# main.net
KiCad netlist of a schematic drawn in EAGLE
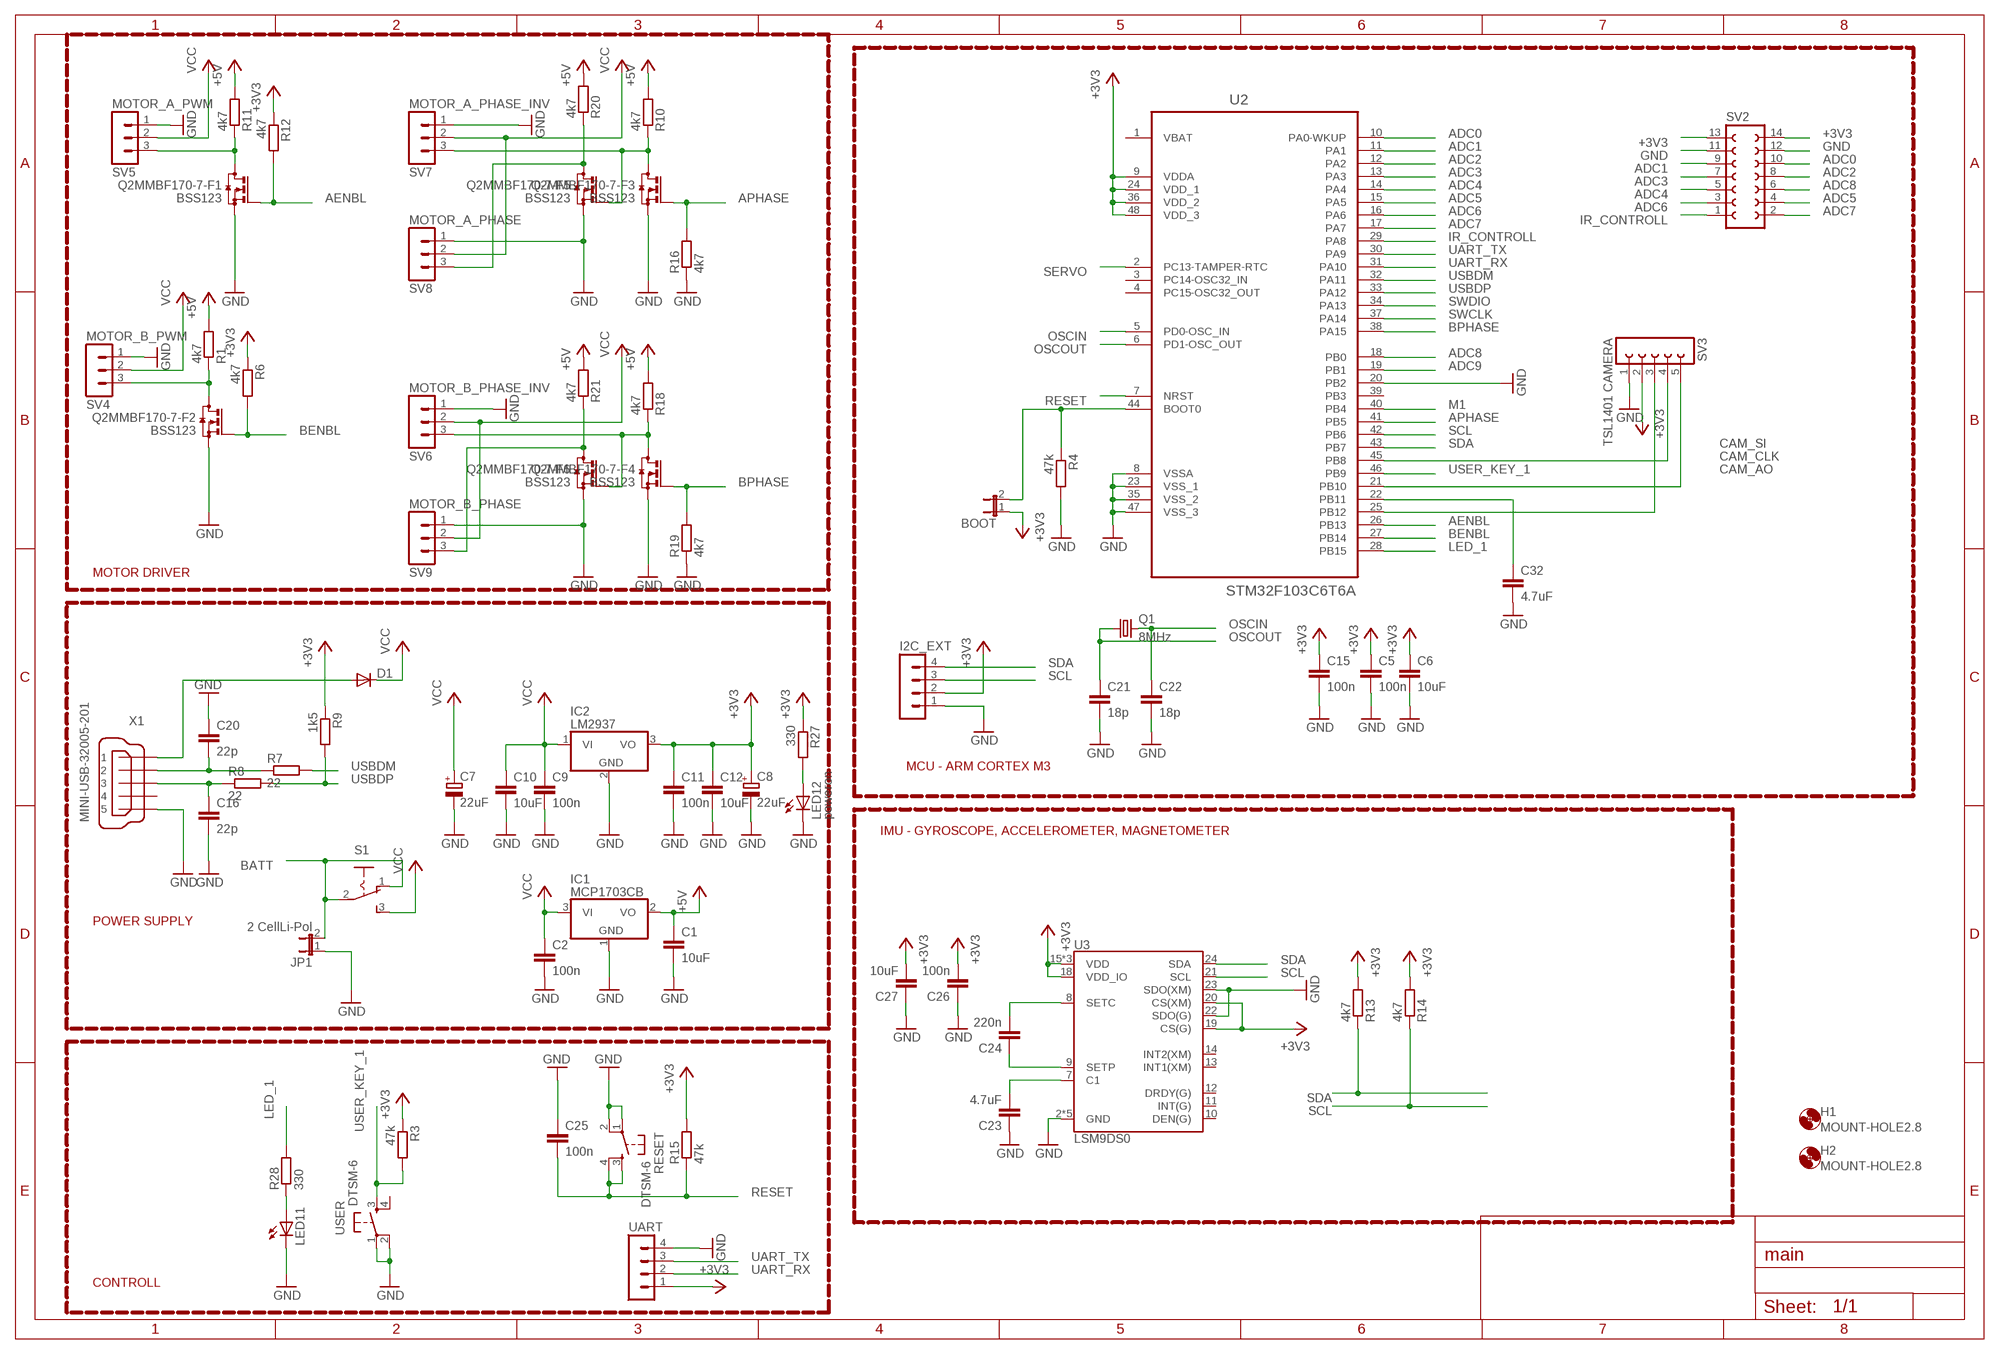
[diagram p0: schematic, sheet 1]

(export (version "E")
  (design (tool "Eeschema 10.0.6"))
  (components
    (comp (ref "BOOT")
      (value "JP1E")
      (footprint "eagle-import:JP1")
      (libsource (lib "eagle-import") (part "JP1E"))
    )
    (comp (ref "C1")
      (value "10uF")
      (footprint "eagle-import:C0805")
      (libsource (lib "eagle-import") (part "C-EUC0805"))
    )
    (comp (ref "C2")
      (value "100n")
      (footprint "eagle-import:C0805")
      (libsource (lib "eagle-import") (part "C-EUC0805"))
    )
    (comp (ref "C5")
      (value "100n")
      (footprint "eagle-import:C0805")
      (libsource (lib "eagle-import") (part "C-EUC0805"))
    )
    (comp (ref "C6")
      (value "10uF")
      (footprint "eagle-import:C0805")
      (libsource (lib "eagle-import") (part "C-EUC0805"))
    )
    (comp (ref "C7")
      (value "22uF")
      (footprint "eagle-import:153CLV-0505")
      (libsource (lib "eagle-import") (part "CPOL-EU153CLV-0505"))
    )
    (comp (ref "C8")
      (value "22uF")
      (footprint "eagle-import:153CLV-0505")
      (libsource (lib "eagle-import") (part "CPOL-EU153CLV-0505"))
    )
    (comp (ref "C9")
      (value "100n")
      (footprint "eagle-import:C0805")
      (libsource (lib "eagle-import") (part "C-EUC0805"))
    )
    (comp (ref "C10")
      (value "10uF")
      (footprint "eagle-import:C0805")
      (libsource (lib "eagle-import") (part "C-EUC0805"))
    )
    (comp (ref "C11")
      (value "100n")
      (footprint "eagle-import:C0805")
      (libsource (lib "eagle-import") (part "C-EUC0805"))
    )
    (comp (ref "C12")
      (value "10uF")
      (footprint "eagle-import:C0805")
      (libsource (lib "eagle-import") (part "C-EUC0805"))
    )
    (comp (ref "C15")
      (value "100n")
      (footprint "eagle-import:C0805")
      (libsource (lib "eagle-import") (part "C-EUC0805"))
    )
    (comp (ref "C16")
      (value "22p")
      (footprint "eagle-import:C0805")
      (libsource (lib "eagle-import") (part "C-EUC0805"))
    )
    (comp (ref "C20")
      (value "22p")
      (footprint "eagle-import:C0805")
      (libsource (lib "eagle-import") (part "C-EUC0805"))
    )
    (comp (ref "C21")
      (value "18p")
      (footprint "eagle-import:C0805")
      (libsource (lib "eagle-import") (part "C-EUC0805"))
    )
    (comp (ref "C22")
      (value "18p")
      (footprint "eagle-import:C0805")
      (libsource (lib "eagle-import") (part "C-EUC0805"))
    )
    (comp (ref "C23")
      (value "4.7uF")
      (footprint "eagle-import:C0805")
      (libsource (lib "eagle-import") (part "C-EUC0805"))
    )
    (comp (ref "C24")
      (value "220n")
      (footprint "eagle-import:C0805")
      (libsource (lib "eagle-import") (part "C-EUC0805"))
    )
    (comp (ref "C25")
      (value "100n")
      (footprint "eagle-import:C0805")
      (libsource (lib "eagle-import") (part "C-EUC0805"))
    )
    (comp (ref "C26")
      (value "100n")
      (footprint "eagle-import:C0805")
      (libsource (lib "eagle-import") (part "C-EUC0805"))
    )
    (comp (ref "C27")
      (value "10uF")
      (footprint "eagle-import:C0805")
      (libsource (lib "eagle-import") (part "C-EUC0805"))
    )
    (comp (ref "C32")
      (value "4.7uF")
      (footprint "eagle-import:C0805")
      (libsource (lib "eagle-import") (part "C-EUC0805"))
    )
    (comp (ref "D1")
      (value "DIODE-SMB")
      (footprint "eagle-import:SMB")
      (libsource (lib "eagle-import") (part "DIODE-SMB"))
    )
    (comp (ref "H1")
      (value "MOUNT-HOLE2.8")
      (footprint "eagle-import:2,8")
      (libsource (lib "eagle-import") (part "MOUNT-HOLE2.8"))
    )
    (comp (ref "H2")
      (value "MOUNT-HOLE2.8")
      (footprint "eagle-import:2,8")
      (libsource (lib "eagle-import") (part "MOUNT-HOLE2.8"))
    )
    (comp (ref "I2C_EXT")
      (value "MA04-1")
      (footprint "eagle-import:MA04-1")
      (libsource (lib "eagle-import") (part "MA04-1"))
    )
    (comp (ref "IC1")
      (value "MCP1703CB")
      (footprint "eagle-import:SOT23")
      (libsource (lib "eagle-import") (part "MCP1703CB"))
    )
    (comp (ref "IC2")
      (value "LM2937")
      (footprint "eagle-import:TO263-3")
      (libsource (lib "eagle-import") (part "LM2937"))
    )
    (comp (ref "JP1")
      (value "2 CellLi-Pol")
      (footprint "eagle-import:JP1")
      (libsource (lib "eagle-import") (part "JP1E"))
    )
    (comp (ref "LED11")
      (value "LEDCHIPLED_1206")
      (footprint "eagle-import:CHIPLED_1206")
      (libsource (lib "eagle-import") (part "LEDCHIPLED_1206"))
    )
    (comp (ref "LED12")
      (value "poweron")
      (footprint "eagle-import:CHIPLED_1206")
      (libsource (lib "eagle-import") (part "LEDCHIPLED_1206"))
    )
    (comp (ref "Q1")
      (value "8MHz")
      (footprint "eagle-import:CTS406")
      (libsource (lib "eagle-import") (part "CRYSTALCTS406"))
    )
    (comp (ref "Q2MMBF170-7-F1")
      (value "BSS123")
      (footprint "eagle-import:SOT23")
      (libsource (lib "eagle-import") (part "BSS123"))
    )
    (comp (ref "Q2MMBF170-7-F2")
      (value "BSS123")
      (footprint "eagle-import:SOT23")
      (libsource (lib "eagle-import") (part "BSS123"))
    )
    (comp (ref "Q2MMBF170-7-F3")
      (value "BSS123")
      (footprint "eagle-import:SOT23")
      (libsource (lib "eagle-import") (part "BSS123"))
    )
    (comp (ref "Q2MMBF170-7-F4")
      (value "BSS123")
      (footprint "eagle-import:SOT23")
      (libsource (lib "eagle-import") (part "BSS123"))
    )
    (comp (ref "Q2MMBF170-7-F5")
      (value "BSS123")
      (footprint "eagle-import:SOT23")
      (libsource (lib "eagle-import") (part "BSS123"))
    )
    (comp (ref "Q2MMBF170-7-F6")
      (value "BSS123")
      (footprint "eagle-import:SOT23")
      (libsource (lib "eagle-import") (part "BSS123"))
    )
    (comp (ref "R1")
      (value "4k7")
      (footprint "eagle-import:M0805")
      (libsource (lib "eagle-import") (part "R-EU_M0805"))
    )
    (comp (ref "R3")
      (value "47k")
      (footprint "eagle-import:M0805")
      (libsource (lib "eagle-import") (part "R-EU_M0805"))
    )
    (comp (ref "R4")
      (value "47k")
      (footprint "eagle-import:M0805")
      (libsource (lib "eagle-import") (part "R-EU_M0805"))
    )
    (comp (ref "R6")
      (value "4k7")
      (footprint "eagle-import:M0805")
      (libsource (lib "eagle-import") (part "R-EU_M0805"))
    )
    (comp (ref "R7")
      (value "22")
      (footprint "eagle-import:M0805")
      (libsource (lib "eagle-import") (part "R-EU_M0805"))
    )
    (comp (ref "R8")
      (value "22")
      (footprint "eagle-import:M0805")
      (libsource (lib "eagle-import") (part "R-EU_M0805"))
    )
    (comp (ref "R9")
      (value "1k5")
      (footprint "eagle-import:M0805")
      (libsource (lib "eagle-import") (part "R-EU_M0805"))
    )
    (comp (ref "R10")
      (value "4k7")
      (footprint "eagle-import:M0805")
      (libsource (lib "eagle-import") (part "R-EU_M0805"))
    )
    (comp (ref "R11")
      (value "4k7")
      (footprint "eagle-import:M0805")
      (libsource (lib "eagle-import") (part "R-EU_M0805"))
    )
    (comp (ref "R12")
      (value "4k7")
      (footprint "eagle-import:M0805")
      (libsource (lib "eagle-import") (part "R-EU_M0805"))
    )
    (comp (ref "R13")
      (value "4k7")
      (footprint "eagle-import:M0805")
      (libsource (lib "eagle-import") (part "R-EU_M0805"))
    )
    (comp (ref "R14")
      (value "4k7")
      (footprint "eagle-import:M0805")
      (libsource (lib "eagle-import") (part "R-EU_M0805"))
    )
    (comp (ref "R15")
      (value "47k")
      (footprint "eagle-import:M0805")
      (libsource (lib "eagle-import") (part "R-EU_M0805"))
    )
    (comp (ref "R16")
      (value "4k7")
      (footprint "eagle-import:M0805")
      (libsource (lib "eagle-import") (part "R-EU_M0805"))
    )
    (comp (ref "R18")
      (value "4k7")
      (footprint "eagle-import:M0805")
      (libsource (lib "eagle-import") (part "R-EU_M0805"))
    )
    (comp (ref "R19")
      (value "4k7")
      (footprint "eagle-import:M0805")
      (libsource (lib "eagle-import") (part "R-EU_M0805"))
    )
    (comp (ref "R20")
      (value "4k7")
      (footprint "eagle-import:M0805")
      (libsource (lib "eagle-import") (part "R-EU_M0805"))
    )
    (comp (ref "R21")
      (value "4k7")
      (footprint "eagle-import:M0805")
      (libsource (lib "eagle-import") (part "R-EU_M0805"))
    )
    (comp (ref "R27")
      (value "330")
      (footprint "eagle-import:M0805")
      (libsource (lib "eagle-import") (part "R-EU_M0805"))
    )
    (comp (ref "R28")
      (value "330")
      (footprint "eagle-import:M0805")
      (libsource (lib "eagle-import") (part "R-EU_M0805"))
    )
    (comp (ref "RESET")
      (value "DTSM-6")
      (footprint "eagle-import:DTSM-6")
      (libsource (lib "eagle-import") (part "DTSM-6"))
    )
    (comp (ref "S1")
      (value "255SB")
      (footprint "eagle-import:255SB")
      (libsource (lib "eagle-import") (part "255SB"))
    )
    (comp (ref "SV2")
      (value "FE07-2")
      (footprint "eagle-import:FE07-2")
      (libsource (lib "eagle-import") (part "FE07-2"))
    )
    (comp (ref "SV3")
      (value "TSL1401 CAMERA")
      (footprint "eagle-import:FE05-1")
      (libsource (lib "eagle-import") (part "FE05-1"))
    )
    (comp (ref "SV4")
      (value "MOTOR_B_PWM")
      (footprint "eagle-import:MA03-1")
      (libsource (lib "eagle-import") (part "MA03-1"))
    )
    (comp (ref "SV5")
      (value "MOTOR_A_PWM")
      (footprint "eagle-import:MA03-1")
      (libsource (lib "eagle-import") (part "MA03-1"))
    )
    (comp (ref "SV6")
      (value "MOTOR_B_PHASE_INV")
      (footprint "eagle-import:MA03-1")
      (libsource (lib "eagle-import") (part "MA03-1"))
    )
    (comp (ref "SV7")
      (value "MOTOR_A_PHASE_INV")
      (footprint "eagle-import:MA03-1")
      (libsource (lib "eagle-import") (part "MA03-1"))
    )
    (comp (ref "SV8")
      (value "MOTOR_A_PHASE")
      (footprint "eagle-import:MA03-1")
      (libsource (lib "eagle-import") (part "MA03-1"))
    )
    (comp (ref "SV9")
      (value "MOTOR_B_PHASE")
      (footprint "eagle-import:MA03-1")
      (libsource (lib "eagle-import") (part "MA03-1"))
    )
    (comp (ref "U2")
      (value "STM32F103C6T6A")
      (footprint "eagle-import:QFP50P900X900X160-48N")
      (libsource (lib "eagle-import") (part "STM32F103C6T6A"))
    )
    (comp (ref "U3")
      (value "LSM9DS0")
      (footprint "eagle-import:LGA-24")
      (libsource (lib "eagle-import") (part "LSM9DS0"))
    )
    (comp (ref "UART")
      (value "MA04-1")
      (footprint "eagle-import:MA04-1")
      (libsource (lib "eagle-import") (part "MA04-1"))
    )
    (comp (ref "USER")
      (value "DTSM-6")
      (footprint "eagle-import:DTSM-6")
      (libsource (lib "eagle-import") (part "DTSM-6"))
    )
    (comp (ref "X1")
      (value "MINI-USB-32005-201")
      (footprint "eagle-import:32005-201")
      (libsource (lib "eagle-import") (part "MINI-USB-32005-201"))
    )
  )
  (nets
    (net (code "1") (name "+3V3") (class "Default")
      (node (ref "BOOT") (pin "1") (pinfunction "1_1") (pintype "passive"))
      (node (ref "C11") (pin "1") (pinfunction "1_1") (pintype "passive"))
      (node (ref "C12") (pin "1") (pinfunction "1_1") (pintype "passive"))
      (node (ref "C15") (pin "1") (pinfunction "1_1") (pintype "passive"))
      (node (ref "C26") (pin "2") (pinfunction "2_2") (pintype "passive"))
      (node (ref "C27") (pin "2") (pinfunction "2_2") (pintype "passive"))
      (node (ref "C5") (pin "1") (pinfunction "1_1") (pintype "passive"))
      (node (ref "C6") (pin "1") (pinfunction "1_1") (pintype "passive"))
      (node (ref "C8") (pin "+") (pinfunction "+_+") (pintype "passive"))
      (node (ref "I2C_EXT") (pin "2") (pinfunction "2_2") (pintype "passive"))
      (node (ref "IC2") (pin "3") (pinfunction "VO_3") (pintype "passive"))
      (node (ref "R12") (pin "1") (pinfunction "1_1") (pintype "passive"))
      (node (ref "R13") (pin "2") (pinfunction "2_2") (pintype "passive"))
      (node (ref "R14") (pin "2") (pinfunction "2_2") (pintype "passive"))
      (node (ref "R15") (pin "2") (pinfunction "2_2") (pintype "passive"))
      (node (ref "R27") (pin "1") (pinfunction "1_1") (pintype "passive"))
      (node (ref "R3") (pin "1") (pinfunction "1_1") (pintype "passive"))
      (node (ref "R6") (pin "1") (pinfunction "1_1") (pintype "passive"))
      (node (ref "R9") (pin "1") (pinfunction "1_1") (pintype "passive"))
      (node (ref "SV2") (pin "13") (pinfunction "13_13") (pintype "passive"))
      (node (ref "SV2") (pin "14") (pinfunction "14_14") (pintype "passive"))
      (node (ref "SV3") (pin "2") (pinfunction "2_2") (pintype "passive"))
      (node (ref "U2") (pin "24") (pinfunction "VDD_1_24") (pintype "power_in"))
      (node (ref "U2") (pin "36") (pinfunction "VDD_2_36") (pintype "power_in"))
      (node (ref "U2") (pin "48") (pinfunction "VDD_3_48") (pintype "power_in"))
      (node (ref "U2") (pin "9") (pinfunction "VDDA_9") (pintype "power_in"))
      (node (ref "U3") (pin "15") (pinfunction "VDD_15") (pintype "bidirectional"))
      (node (ref "U3") (pin "16") (pinfunction "VDD_16") (pintype "bidirectional"))
      (node (ref "U3") (pin "17") (pinfunction "VDD_17") (pintype "bidirectional"))
      (node (ref "U3") (pin "18") (pinfunction "VDD_IO_18") (pintype "bidirectional"))
      (node (ref "U3") (pin "19") (pinfunction "CS(G)_19") (pintype "bidirectional"))
      (node (ref "U3") (pin "20") (pinfunction "CS(XM)_20") (pintype "bidirectional"))
      (node (ref "UART") (pin "1") (pinfunction "1_1") (pintype "passive"))
    )
    (net (code "2") (name "+5V") (class "Default")
      (node (ref "C1") (pin "1") (pinfunction "1_1") (pintype "passive"))
      (node (ref "IC1") (pin "2") (pinfunction "VO_2") (pintype "passive"))
      (node (ref "R1") (pin "2") (pinfunction "2_2") (pintype "passive"))
      (node (ref "R10") (pin "2") (pinfunction "2_2") (pintype "passive"))
      (node (ref "R11") (pin "2") (pinfunction "2_2") (pintype "passive"))
      (node (ref "R18") (pin "2") (pinfunction "2_2") (pintype "passive"))
      (node (ref "R20") (pin "2") (pinfunction "2_2") (pintype "passive"))
      (node (ref "R21") (pin "2") (pinfunction "2_2") (pintype "passive"))
    )
    (net (code "3") (name "/ADC0") (class "Default")
      (node (ref "SV2") (pin "10") (pinfunction "10_10") (pintype "passive"))
      (node (ref "U2") (pin "10") (pinfunction "PA0-WKUP_10") (pintype "bidirectional"))
    )
    (net (code "4") (name "/ADC1") (class "Default")
      (node (ref "SV2") (pin "9") (pinfunction "9_9") (pintype "passive"))
      (node (ref "U2") (pin "11") (pinfunction "PA1_11") (pintype "bidirectional"))
    )
    (net (code "5") (name "/ADC2") (class "Default")
      (node (ref "SV2") (pin "8") (pinfunction "8_8") (pintype "passive"))
      (node (ref "U2") (pin "12") (pinfunction "PA2_12") (pintype "bidirectional"))
    )
    (net (code "6") (name "/ADC3") (class "Default")
      (node (ref "SV2") (pin "7") (pinfunction "7_7") (pintype "passive"))
      (node (ref "U2") (pin "13") (pinfunction "PA3_13") (pintype "bidirectional"))
    )
    (net (code "7") (name "/ADC4") (class "Default")
      (node (ref "SV2") (pin "5") (pinfunction "5_5") (pintype "passive"))
      (node (ref "U2") (pin "14") (pinfunction "PA4_14") (pintype "bidirectional"))
    )
    (net (code "8") (name "/ADC5") (class "Default")
      (node (ref "SV2") (pin "4") (pinfunction "4_4") (pintype "passive"))
      (node (ref "U2") (pin "15") (pinfunction "PA5_15") (pintype "bidirectional"))
    )
    (net (code "9") (name "/ADC6") (class "Default")
      (node (ref "SV2") (pin "3") (pinfunction "3_3") (pintype "passive"))
      (node (ref "U2") (pin "16") (pinfunction "PA6_16") (pintype "bidirectional"))
    )
    (net (code "10") (name "/ADC7") (class "Default")
      (node (ref "SV2") (pin "2") (pinfunction "2_2") (pintype "passive"))
      (node (ref "U2") (pin "17") (pinfunction "PA7_17") (pintype "bidirectional"))
    )
    (net (code "11") (name "/ADC8") (class "Default")
      (node (ref "SV2") (pin "6") (pinfunction "6_6") (pintype "passive"))
      (node (ref "U2") (pin "18") (pinfunction "PB0_18") (pintype "bidirectional"))
    )
    (net (code "12") (name "/ADC9") (class "Default")
      (node (ref "U2") (pin "19") (pinfunction "PB1_19") (pintype "bidirectional"))
    )
    (net (code "13") (name "/AENBL") (class "Default")
      (node (ref "Q2MMBF170-7-F1") (pin "1") (pinfunction "G_1") (pintype "passive"))
      (node (ref "R12") (pin "2") (pinfunction "2_2") (pintype "passive"))
      (node (ref "U2") (pin "26") (pinfunction "PB13_26") (pintype "bidirectional"))
    )
    (net (code "14") (name "/APHASE") (class "Default")
      (node (ref "Q2MMBF170-7-F3") (pin "1") (pinfunction "G_1") (pintype "passive"))
      (node (ref "R16") (pin "2") (pinfunction "2_2") (pintype "passive"))
      (node (ref "U2") (pin "41") (pinfunction "PB5_41") (pintype "bidirectional"))
    )
    (net (code "15") (name "/BATT") (class "Default")
      (node (ref "JP1") (pin "2") (pinfunction "2_2") (pintype "passive"))
      (node (ref "S1") (pin "1") (pinfunction "O_1") (pintype "passive"))
      (node (ref "S1") (pin "2") (pinfunction "P_2") (pintype "passive"))
    )
    (net (code "16") (name "/BENBL") (class "Default")
      (node (ref "Q2MMBF170-7-F2") (pin "1") (pinfunction "G_1") (pintype "passive"))
      (node (ref "R6") (pin "2") (pinfunction "2_2") (pintype "passive"))
      (node (ref "U2") (pin "27") (pinfunction "PB14_27") (pintype "bidirectional"))
    )
    (net (code "17") (name "/BPHASE") (class "Default")
      (node (ref "Q2MMBF170-7-F4") (pin "1") (pinfunction "G_1") (pintype "passive"))
      (node (ref "R19") (pin "2") (pinfunction "2_2") (pintype "passive"))
      (node (ref "U2") (pin "38") (pinfunction "PA15_38") (pintype "bidirectional"))
    )
    (net (code "18") (name "/CAM_AO") (class "Default")
      (node (ref "SV3") (pin "3") (pinfunction "3_3") (pintype "passive"))
      (node (ref "U2") (pin "25") (pinfunction "PB12_25") (pintype "bidirectional"))
    )
    (net (code "19") (name "/CAM_CLK") (class "Default")
      (node (ref "SV3") (pin "4") (pinfunction "4_4") (pintype "passive"))
      (node (ref "U2") (pin "45") (pinfunction "PB8_45") (pintype "bidirectional"))
    )
    (net (code "20") (name "/CAM_SI") (class "Default")
      (node (ref "SV3") (pin "5") (pinfunction "5_5") (pintype "passive"))
      (node (ref "U2") (pin "21") (pinfunction "PB10_21") (pintype "bidirectional"))
    )
    (net (code "21") (name "/IR_CONTROLL") (class "Default")
      (node (ref "SV2") (pin "1") (pinfunction "1_1") (pintype "passive"))
      (node (ref "U2") (pin "29") (pinfunction "PA8_29") (pintype "bidirectional"))
    )
    (net (code "22") (name "/LED_1") (class "Default")
      (node (ref "R28") (pin "2") (pinfunction "2_2") (pintype "passive"))
      (node (ref "U2") (pin "28") (pinfunction "PB15_28") (pintype "bidirectional"))
    )
    (net (code "23") (name "/M1") (class "Default")
      (node (ref "U2") (pin "40") (pinfunction "PB4_40") (pintype "bidirectional"))
    )
    (net (code "24") (name "/OSCIN") (class "Default")
      (node (ref "C22") (pin "1") (pinfunction "1_1") (pintype "passive"))
      (node (ref "Q1") (pin "3") (pinfunction "2_3") (pintype "passive"))
      (node (ref "U2") (pin "5") (pinfunction "PD0-OSC_IN_5") (pintype "bidirectional"))
    )
    (net (code "25") (name "/OSCOUT") (class "Default")
      (node (ref "C21") (pin "1") (pinfunction "1_1") (pintype "passive"))
      (node (ref "Q1") (pin "1") (pinfunction "1_1") (pintype "passive"))
      (node (ref "U2") (pin "6") (pinfunction "PD1-OSC_OUT_6") (pintype "bidirectional"))
    )
    (net (code "26") (name "/RESET") (class "Default")
      (node (ref "C25") (pin "2") (pinfunction "2_2") (pintype "passive"))
      (node (ref "R15") (pin "1") (pinfunction "1_1") (pintype "passive"))
      (node (ref "RESET") (pin "3") (pinfunction "3_3") (pintype "passive"))
      (node (ref "RESET") (pin "4") (pinfunction "4_4") (pintype "passive"))
      (node (ref "U2") (pin "7") (pinfunction "NRST_7") (pintype "bidirectional"))
    )
    (net (code "27") (name "/SCL") (class "Default")
      (node (ref "I2C_EXT") (pin "3") (pinfunction "3_3") (pintype "passive"))
      (node (ref "R14") (pin "1") (pinfunction "1_1") (pintype "passive"))
      (node (ref "U2") (pin "42") (pinfunction "PB6_42") (pintype "bidirectional"))
      (node (ref "U3") (pin "21") (pinfunction "SCL_21") (pintype "bidirectional"))
    )
    (net (code "28") (name "/SDA") (class "Default")
      (node (ref "I2C_EXT") (pin "4") (pinfunction "4_4") (pintype "passive"))
      (node (ref "R13") (pin "1") (pinfunction "1_1") (pintype "passive"))
      (node (ref "U2") (pin "43") (pinfunction "PB7_43") (pintype "bidirectional"))
      (node (ref "U3") (pin "24") (pinfunction "SDA_24") (pintype "bidirectional"))
    )
    (net (code "29") (name "/SERVO") (class "Default")
      (node (ref "U2") (pin "2") (pinfunction "PC13-TAMPER-RTC_2") (pintype "bidirectional"))
    )
    (net (code "30") (name "/SWCLK") (class "Default")
      (node (ref "U2") (pin "37") (pinfunction "PA14_37") (pintype "bidirectional"))
    )
    (net (code "31") (name "/SWDIO") (class "Default")
      (node (ref "U2") (pin "34") (pinfunction "PA13_34") (pintype "bidirectional"))
    )
    (net (code "32") (name "/UART_RX") (class "Default")
      (node (ref "U2") (pin "31") (pinfunction "PA10_31") (pintype "bidirectional"))
      (node (ref "UART") (pin "2") (pinfunction "2_2") (pintype "passive"))
    )
    (net (code "33") (name "/UART_TX") (class "Default")
      (node (ref "U2") (pin "30") (pinfunction "PA9_30") (pintype "bidirectional"))
      (node (ref "UART") (pin "3") (pinfunction "3_3") (pintype "passive"))
    )
    (net (code "34") (name "/USBDM") (class "Default")
      (node (ref "R7") (pin "2") (pinfunction "2_2") (pintype "passive"))
      (node (ref "U2") (pin "32") (pinfunction "PA11_32") (pintype "bidirectional"))
    )
    (net (code "35") (name "/USBDP") (class "Default")
      (node (ref "R8") (pin "2") (pinfunction "2_2") (pintype "passive"))
      (node (ref "R9") (pin "2") (pinfunction "2_2") (pintype "passive"))
      (node (ref "U2") (pin "33") (pinfunction "PA12_33") (pintype "bidirectional"))
    )
    (net (code "36") (name "/USER_KEY_1") (class "Default")
      (node (ref "R3") (pin "2") (pinfunction "2_2") (pintype "passive"))
      (node (ref "U2") (pin "46") (pinfunction "PB9_46") (pintype "bidirectional"))
      (node (ref "USER") (pin "3") (pinfunction "3_3") (pintype "passive"))
    )
    (net (code "37") (name "/VBAT") (class "Default")
      (node (ref "U2") (pin "1") (pinfunction "VBAT_1") (pintype "power_in"))
    )
    (net (code "38") (name "GND") (class "Default")
      (node (ref "C1") (pin "2") (pinfunction "2_2") (pintype "passive"))
      (node (ref "C10") (pin "2") (pinfunction "2_2") (pintype "passive"))
      (node (ref "C11") (pin "2") (pinfunction "2_2") (pintype "passive"))
      (node (ref "C12") (pin "2") (pinfunction "2_2") (pintype "passive"))
      (node (ref "C15") (pin "2") (pinfunction "2_2") (pintype "passive"))
      (node (ref "C16") (pin "2") (pinfunction "2_2") (pintype "passive"))
      (node (ref "C2") (pin "2") (pinfunction "2_2") (pintype "passive"))
      (node (ref "C20") (pin "1") (pinfunction "1_1") (pintype "passive"))
      (node (ref "C21") (pin "2") (pinfunction "2_2") (pintype "passive"))
      (node (ref "C22") (pin "2") (pinfunction "2_2") (pintype "passive"))
      (node (ref "C23") (pin "1") (pinfunction "1_1") (pintype "passive"))
      (node (ref "C25") (pin "1") (pinfunction "1_1") (pintype "passive"))
      (node (ref "C26") (pin "1") (pinfunction "1_1") (pintype "passive"))
      (node (ref "C27") (pin "1") (pinfunction "1_1") (pintype "passive"))
      (node (ref "C32") (pin "2") (pinfunction "2_2") (pintype "passive"))
      (node (ref "C5") (pin "2") (pinfunction "2_2") (pintype "passive"))
      (node (ref "C6") (pin "2") (pinfunction "2_2") (pintype "passive"))
      (node (ref "C7") (pin "-") (pinfunction "-_-") (pintype "passive"))
      (node (ref "C8") (pin "-") (pinfunction "-_-") (pintype "passive"))
      (node (ref "C9") (pin "2") (pinfunction "2_2") (pintype "passive"))
      (node (ref "I2C_EXT") (pin "1") (pinfunction "1_1") (pintype "passive"))
      (node (ref "IC1") (pin "1") (pinfunction "GND_1") (pintype "passive"))
      (node (ref "IC2") (pin "2") (pinfunction "GND_2") (pintype "passive"))
      (node (ref "JP1") (pin "1") (pinfunction "1_1") (pintype "passive"))
      (node (ref "LED11") (pin "C") (pinfunction "C_C") (pintype "passive"))
      (node (ref "LED12") (pin "C") (pinfunction "C_C") (pintype "passive"))
      (node (ref "Q2MMBF170-7-F1") (pin "2") (pinfunction "S_2") (pintype "passive"))
      (node (ref "Q2MMBF170-7-F2") (pin "2") (pinfunction "S_2") (pintype "passive"))
      (node (ref "Q2MMBF170-7-F3") (pin "2") (pinfunction "S_2") (pintype "passive"))
      (node (ref "Q2MMBF170-7-F4") (pin "2") (pinfunction "S_2") (pintype "passive"))
      (node (ref "Q2MMBF170-7-F5") (pin "2") (pinfunction "S_2") (pintype "passive"))
      (node (ref "Q2MMBF170-7-F6") (pin "2") (pinfunction "S_2") (pintype "passive"))
      (node (ref "R16") (pin "1") (pinfunction "1_1") (pintype "passive"))
      (node (ref "R19") (pin "1") (pinfunction "1_1") (pintype "passive"))
      (node (ref "R4") (pin "2") (pinfunction "2_2") (pintype "passive"))
      (node (ref "RESET") (pin "1") (pinfunction "1_1") (pintype "passive"))
      (node (ref "RESET") (pin "2") (pinfunction "2_2") (pintype "passive"))
      (node (ref "SV2") (pin "11") (pinfunction "11_11") (pintype "passive"))
      (node (ref "SV2") (pin "12") (pinfunction "12_12") (pintype "passive"))
      (node (ref "SV3") (pin "1") (pinfunction "1_1") (pintype "passive"))
      (node (ref "SV4") (pin "1") (pinfunction "1_1") (pintype "passive"))
      (node (ref "SV5") (pin "1") (pinfunction "1_1") (pintype "passive"))
      (node (ref "SV6") (pin "1") (pinfunction "1_1") (pintype "passive"))
      (node (ref "SV7") (pin "1") (pinfunction "1_1") (pintype "passive"))
      (node (ref "SV8") (pin "1") (pinfunction "1_1") (pintype "passive"))
      (node (ref "SV9") (pin "1") (pinfunction "1_1") (pintype "passive"))
      (node (ref "U2") (pin "20") (pinfunction "PB2_20") (pintype "bidirectional"))
      (node (ref "U2") (pin "23") (pinfunction "VSS_1_23") (pintype "passive"))
      (node (ref "U2") (pin "35") (pinfunction "VSS_2_35") (pintype "passive"))
      (node (ref "U2") (pin "47") (pinfunction "VSS_3_47") (pintype "passive"))
      (node (ref "U2") (pin "8") (pinfunction "VSSA_8") (pintype "passive"))
      (node (ref "U3") (pin "2") (pinfunction "GND_2") (pintype "bidirectional"))
      (node (ref "U3") (pin "22") (pinfunction "SDO(G)_22") (pintype "bidirectional"))
      (node (ref "U3") (pin "23") (pinfunction "SDO(XM)_23") (pintype "bidirectional"))
      (node (ref "U3") (pin "3") (pinfunction "GND_3") (pintype "bidirectional"))
      (node (ref "U3") (pin "4") (pinfunction "GND_4") (pintype "bidirectional"))
      (node (ref "U3") (pin "5") (pinfunction "GND_5") (pintype "bidirectional"))
      (node (ref "U3") (pin "6") (pinfunction "GND_6") (pintype "bidirectional"))
      (node (ref "UART") (pin "4") (pinfunction "4_4") (pintype "passive"))
      (node (ref "USER") (pin "1") (pinfunction "1_1") (pintype "passive"))
      (node (ref "USER") (pin "2") (pinfunction "2_2") (pintype "passive"))
      (node (ref "X1") (pin "5") (pinfunction "5_5") (pintype "passive"))
    )
    (net (code "39") (name "Net-(C16-Pad1)") (class "Default")
      (node (ref "C16") (pin "1") (pinfunction "1_1") (pintype "passive"))
      (node (ref "R8") (pin "1") (pinfunction "1_1") (pintype "passive"))
      (node (ref "X1") (pin "3") (pinfunction "3_3") (pintype "passive"))
    )
    (net (code "40") (name "Net-(C20-Pad2)") (class "Default")
      (node (ref "C20") (pin "2") (pinfunction "2_2") (pintype "passive"))
      (node (ref "R7") (pin "1") (pinfunction "1_1") (pintype "passive"))
      (node (ref "X1") (pin "2") (pinfunction "2_2") (pintype "passive"))
    )
    (net (code "41") (name "Net-(D1-PadA)") (class "Default")
      (node (ref "D1") (pin "A") (pinfunction "A_A") (pintype "passive"))
      (node (ref "X1") (pin "1") (pinfunction "1_1") (pintype "passive"))
    )
    (net (code "42") (name "Net-(LED11-PadA)") (class "Default")
      (node (ref "LED11") (pin "A") (pinfunction "A_A") (pintype "passive"))
      (node (ref "R28") (pin "1") (pinfunction "1_1") (pintype "passive"))
    )
    (net (code "43") (name "Net-(LED12-PadA)") (class "Default")
      (node (ref "LED12") (pin "A") (pinfunction "A_A") (pintype "passive"))
      (node (ref "R27") (pin "2") (pinfunction "2_2") (pintype "passive"))
    )
    (net (code "44") (name "Net-(Q2MMBF170-7-F1-D)") (class "Default")
      (node (ref "Q2MMBF170-7-F1") (pin "3") (pinfunction "D_3") (pintype "passive"))
      (node (ref "R11") (pin "1") (pinfunction "1_1") (pintype "passive"))
      (node (ref "SV5") (pin "3") (pinfunction "3_3") (pintype "passive"))
    )
    (net (code "45") (name "Net-(Q2MMBF170-7-F2-D)") (class "Default")
      (node (ref "Q2MMBF170-7-F2") (pin "3") (pinfunction "D_3") (pintype "passive"))
      (node (ref "R1") (pin "1") (pinfunction "1_1") (pintype "passive"))
      (node (ref "SV4") (pin "3") (pinfunction "3_3") (pintype "passive"))
    )
    (net (code "46") (name "Net-(Q2MMBF170-7-F3-D)") (class "Default")
      (node (ref "Q2MMBF170-7-F3") (pin "3") (pinfunction "D_3") (pintype "passive"))
      (node (ref "Q2MMBF170-7-F5") (pin "1") (pinfunction "G_1") (pintype "passive"))
      (node (ref "R10") (pin "1") (pinfunction "1_1") (pintype "passive"))
      (node (ref "SV7") (pin "3") (pinfunction "3_3") (pintype "passive"))
    )
    (net (code "47") (name "Net-(Q2MMBF170-7-F4-D)") (class "Default")
      (node (ref "Q2MMBF170-7-F4") (pin "3") (pinfunction "D_3") (pintype "passive"))
      (node (ref "Q2MMBF170-7-F6") (pin "1") (pinfunction "G_1") (pintype "passive"))
      (node (ref "R18") (pin "1") (pinfunction "1_1") (pintype "passive"))
      (node (ref "SV6") (pin "3") (pinfunction "3_3") (pintype "passive"))
    )
    (net (code "48") (name "Net-(Q2MMBF170-7-F5-D)") (class "Default")
      (node (ref "Q2MMBF170-7-F5") (pin "3") (pinfunction "D_3") (pintype "passive"))
      (node (ref "R20") (pin "1") (pinfunction "1_1") (pintype "passive"))
      (node (ref "SV8") (pin "3") (pinfunction "3_3") (pintype "passive"))
    )
    (net (code "49") (name "Net-(Q2MMBF170-7-F6-D)") (class "Default")
      (node (ref "Q2MMBF170-7-F6") (pin "3") (pinfunction "D_3") (pintype "passive"))
      (node (ref "R21") (pin "1") (pinfunction "1_1") (pintype "passive"))
      (node (ref "SV9") (pin "3") (pinfunction "3_3") (pintype "passive"))
    )
    (net (code "50") (name "Net-(U2-BOOT0)") (class "Default")
      (node (ref "BOOT") (pin "2") (pinfunction "2_2") (pintype "passive"))
      (node (ref "R4") (pin "1") (pinfunction "1_1") (pintype "passive"))
      (node (ref "U2") (pin "44") (pinfunction "BOOT0_44") (pintype "input"))
    )
    (net (code "51") (name "Net-(U2-PB11)") (class "Default")
      (node (ref "C32") (pin "1") (pinfunction "1_1") (pintype "passive"))
      (node (ref "U2") (pin "22") (pinfunction "PB11_22") (pintype "bidirectional"))
    )
    (net (code "52") (name "Net-(U3-C1)") (class "Default")
      (node (ref "C23") (pin "2") (pinfunction "2_2") (pintype "passive"))
      (node (ref "U3") (pin "7") (pinfunction "C1_7") (pintype "bidirectional"))
    )
    (net (code "53") (name "Net-(U3-SETC)") (class "Default")
      (node (ref "C24") (pin "2") (pinfunction "2_2") (pintype "passive"))
      (node (ref "U3") (pin "8") (pinfunction "SETC_8") (pintype "bidirectional"))
    )
    (net (code "54") (name "Net-(U3-SETP)") (class "Default")
      (node (ref "C24") (pin "1") (pinfunction "1_1") (pintype "passive"))
      (node (ref "U3") (pin "9") (pinfunction "SETP_9") (pintype "bidirectional"))
    )
    (net (code "55") (name "VCC") (class "Default")
      (node (ref "C10") (pin "1") (pinfunction "1_1") (pintype "passive"))
      (node (ref "C2") (pin "1") (pinfunction "1_1") (pintype "passive"))
      (node (ref "C7") (pin "+") (pinfunction "+_+") (pintype "passive"))
      (node (ref "C9") (pin "1") (pinfunction "1_1") (pintype "passive"))
      (node (ref "D1") (pin "C") (pinfunction "C_C") (pintype "passive"))
      (node (ref "IC1") (pin "3") (pinfunction "VI_3") (pintype "input"))
      (node (ref "IC2") (pin "1") (pinfunction "VI_1") (pintype "input"))
      (node (ref "S1") (pin "3") (pinfunction "S_3") (pintype "passive"))
      (node (ref "SV4") (pin "2") (pinfunction "2_2") (pintype "passive"))
      (node (ref "SV5") (pin "2") (pinfunction "2_2") (pintype "passive"))
      (node (ref "SV6") (pin "2") (pinfunction "2_2") (pintype "passive"))
      (node (ref "SV7") (pin "2") (pinfunction "2_2") (pintype "passive"))
      (node (ref "SV8") (pin "2") (pinfunction "2_2") (pintype "passive"))
      (node (ref "SV9") (pin "2") (pinfunction "2_2") (pintype "passive"))
    )
    (net (code "56") (name "unconnected-(U2-PB3-Pad39)") (class "Default")
      (node (ref "U2") (pin "39") (pinfunction "PB3_39") (pintype "bidirectional"))
    )
    (net (code "57") (name "unconnected-(U2-PC14-OSC32_IN-Pad3)") (class "Default")
      (node (ref "U2") (pin "3") (pinfunction "PC14-OSC32_IN_3") (pintype "bidirectional"))
    )
    (net (code "58") (name "unconnected-(U2-PC15-OSC32_OUT-Pad4)") (class "Default")
      (node (ref "U2") (pin "4") (pinfunction "PC15-OSC32_OUT_4") (pintype "bidirectional"))
    )
    (net (code "59") (name "unconnected-(U3-DEN(G)-Pad10)") (class "Default")
      (node (ref "U3") (pin "10") (pinfunction "DEN(G)_10") (pintype "bidirectional"))
    )
    (net (code "60") (name "unconnected-(U3-DRDY(G)-Pad12)") (class "Default")
      (node (ref "U3") (pin "12") (pinfunction "DRDY(G)_12") (pintype "bidirectional"))
    )
    (net (code "61") (name "unconnected-(U3-INT(G)-Pad11)") (class "Default")
      (node (ref "U3") (pin "11") (pinfunction "INT(G)_11") (pintype "bidirectional"))
    )
    (net (code "62") (name "unconnected-(U3-INT1(XM)-Pad13)") (class "Default")
      (node (ref "U3") (pin "13") (pinfunction "INT1(XM)_13") (pintype "bidirectional"))
    )
    (net (code "63") (name "unconnected-(U3-INT2(XM)-Pad14)") (class "Default")
      (node (ref "U3") (pin "14") (pinfunction "INT2(XM)_14") (pintype "bidirectional"))
    )
    (net (code "64") (name "unconnected-(USER-Pad4)") (class "Default")
      (node (ref "USER") (pin "4") (pinfunction "4_4") (pintype "passive"))
    )
    (net (code "65") (name "unconnected-(X1-Pad4)") (class "Default")
      (node (ref "X1") (pin "4") (pinfunction "4_4") (pintype "passive"))
    )
  )
)
